# LoadCellAmp.net
KiCad netlist of a schematic drawn in EAGLE
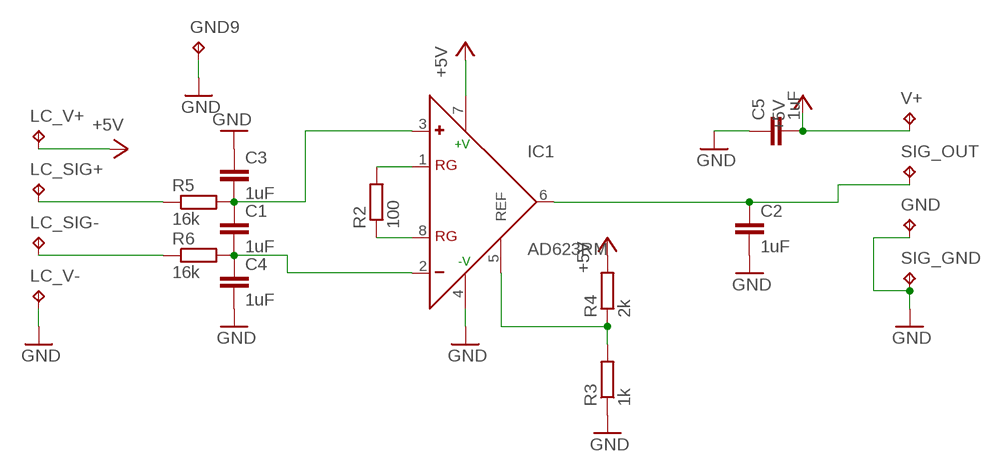
[diagram p0: schematic, sheet 1]

(export (version "E")
  (design (tool "Eeschema 10.0.6"))
  (components
    (comp (ref "C1")
      (value "1uF")
      (footprint "eagle-import:C0805")
      (libsource (lib "eagle-import") (part "C-EUC0805"))
    )
    (comp (ref "C2")
      (value "1uF")
      (footprint "eagle-import:C0805")
      (libsource (lib "eagle-import") (part "C-EUC0805"))
    )
    (comp (ref "C3")
      (value "1uF")
      (footprint "eagle-import:C0805")
      (libsource (lib "eagle-import") (part "C-EUC0805"))
    )
    (comp (ref "C4")
      (value "1uF")
      (footprint "eagle-import:C0805")
      (libsource (lib "eagle-import") (part "C-EUC0805"))
    )
    (comp (ref "C5")
      (value "1uF")
      (footprint "eagle-import:C0805")
      (libsource (lib "eagle-import") (part "C-EUC0805"))
    )
    (comp (ref "GND")
      (value "TPB1,27")
      (footprint "eagle-import:B1,27")
      (libsource (lib "eagle-import") (part "TPB1,27"))
    )
    (comp (ref "GND9")
      (value "TPB1,27")
      (footprint "eagle-import:B1,27")
      (libsource (lib "eagle-import") (part "TPB1,27"))
    )
    (comp (ref "IC1")
      (value "AD623RM")
      (footprint "eagle-import:MSOP08")
      (fields (field (name "MPN") "AD623ARMZ"))
      (libsource (lib "eagle-import") (part "AD623RM"))
    )
    (comp (ref "LC_SIG+")
      (value "TPB1,27")
      (footprint "eagle-import:B1,27")
      (libsource (lib "eagle-import") (part "TPB1,27"))
    )
    (comp (ref "LC_SIG-")
      (value "TPB1,27")
      (footprint "eagle-import:B1,27")
      (libsource (lib "eagle-import") (part "TPB1,27"))
    )
    (comp (ref "LC_V+")
      (value "TPB1,27")
      (footprint "eagle-import:B1,27")
      (libsource (lib "eagle-import") (part "TPB1,27"))
    )
    (comp (ref "LC_V-")
      (value "TPB1,27")
      (footprint "eagle-import:B1,27")
      (libsource (lib "eagle-import") (part "TPB1,27"))
    )
    (comp (ref "R2")
      (value "100")
      (footprint "eagle-import:R0805")
      (libsource (lib "eagle-import") (part "R-EU_R0805"))
    )
    (comp (ref "R3")
      (value "1k")
      (footprint "eagle-import:R0805")
      (libsource (lib "eagle-import") (part "R-EU_R0805"))
    )
    (comp (ref "R4")
      (value "2k")
      (footprint "eagle-import:R0805")
      (libsource (lib "eagle-import") (part "R-EU_R0805"))
    )
    (comp (ref "R5")
      (value "16k")
      (footprint "eagle-import:R0805")
      (libsource (lib "eagle-import") (part "R-EU_R0805"))
    )
    (comp (ref "R6")
      (value "16k")
      (footprint "eagle-import:R0805")
      (libsource (lib "eagle-import") (part "R-EU_R0805"))
    )
    (comp (ref "SIG_GND")
      (value "TPB1,27")
      (footprint "eagle-import:B1,27")
      (libsource (lib "eagle-import") (part "TPB1,27"))
    )
    (comp (ref "SIG_OUT")
      (value "TPB1,27")
      (footprint "eagle-import:B1,27")
      (libsource (lib "eagle-import") (part "TPB1,27"))
    )
    (comp (ref "V+")
      (value "TPB1,27")
      (footprint "eagle-import:B1,27")
      (libsource (lib "eagle-import") (part "TPB1,27"))
    )
  )
  (nets
    (net (code "1") (name "+5V") (class "Default")
      (node (ref "C5") (pin "2") (pinfunction "2_2") (pintype "passive"))
      (node (ref "IC1") (pin "7") (pinfunction "+V_7") (pintype "power_in"))
      (node (ref "LC_V+") (pin "TP") (pinfunction "TP_TP") (pintype "input"))
      (node (ref "R4") (pin "2") (pinfunction "2_2") (pintype "passive"))
      (node (ref "V+") (pin "TP") (pinfunction "TP_TP") (pintype "input"))
    )
    (net (code "2") (name "GND") (class "Default")
      (node (ref "C2") (pin "2") (pinfunction "2_2") (pintype "passive"))
      (node (ref "C3") (pin "1") (pinfunction "1_1") (pintype "passive"))
      (node (ref "C4") (pin "2") (pinfunction "2_2") (pintype "passive"))
      (node (ref "C5") (pin "1") (pinfunction "1_1") (pintype "passive"))
      (node (ref "GND") (pin "TP") (pinfunction "TP_TP") (pintype "input"))
      (node (ref "GND9") (pin "TP") (pinfunction "TP_TP") (pintype "input"))
      (node (ref "IC1") (pin "4") (pinfunction "-V_4") (pintype "power_in"))
      (node (ref "LC_V-") (pin "TP") (pinfunction "TP_TP") (pintype "input"))
      (node (ref "R3") (pin "1") (pinfunction "1_1") (pintype "passive"))
      (node (ref "SIG_GND") (pin "TP") (pinfunction "TP_TP") (pintype "input"))
    )
    (net (code "3") (name "Net-(IC1-+)") (class "Default")
      (node (ref "C1") (pin "1") (pinfunction "1_1") (pintype "passive"))
      (node (ref "C3") (pin "2") (pinfunction "2_2") (pintype "passive"))
      (node (ref "IC1") (pin "3") (pinfunction "+_3") (pintype "input"))
      (node (ref "R5") (pin "2") (pinfunction "2_2") (pintype "passive"))
    )
    (net (code "4") (name "Net-(IC1--)") (class "Default")
      (node (ref "C1") (pin "2") (pinfunction "2_2") (pintype "passive"))
      (node (ref "C4") (pin "1") (pinfunction "1_1") (pintype "passive"))
      (node (ref "IC1") (pin "2") (pinfunction "-_2") (pintype "input"))
      (node (ref "R6") (pin "2") (pinfunction "2_2") (pintype "passive"))
    )
    (net (code "5") (name "Net-(IC1-OUT)") (class "Default")
      (node (ref "C2") (pin "1") (pinfunction "1_1") (pintype "passive"))
      (node (ref "IC1") (pin "6") (pinfunction "OUT_6") (pintype "output"))
      (node (ref "SIG_OUT") (pin "TP") (pinfunction "TP_TP") (pintype "input"))
    )
    (net (code "6") (name "Net-(IC1-REF)") (class "Default")
      (node (ref "IC1") (pin "5") (pinfunction "REF_5") (pintype "passive"))
      (node (ref "R3") (pin "2") (pinfunction "2_2") (pintype "passive"))
      (node (ref "R4") (pin "1") (pinfunction "1_1") (pintype "passive"))
    )
    (net (code "7") (name "Net-(IC1-RG-Pad1)") (class "Default")
      (node (ref "IC1") (pin "1") (pinfunction "RG_1") (pintype "passive"))
      (node (ref "R2") (pin "2") (pinfunction "2_2") (pintype "passive"))
    )
    (net (code "8") (name "Net-(IC1-RG-Pad8)") (class "Default")
      (node (ref "IC1") (pin "8") (pinfunction "RG_8") (pintype "passive"))
      (node (ref "R2") (pin "1") (pinfunction "1_1") (pintype "passive"))
    )
    (net (code "9") (name "Net-(LC_SIG+-PadTP)") (class "Default")
      (node (ref "LC_SIG+") (pin "TP") (pinfunction "TP_TP") (pintype "input"))
      (node (ref "R5") (pin "1") (pinfunction "1_1") (pintype "passive"))
    )
    (net (code "10") (name "Net-(LC_SIG--PadTP)") (class "Default")
      (node (ref "LC_SIG-") (pin "TP") (pinfunction "TP_TP") (pintype "input"))
      (node (ref "R6") (pin "1") (pinfunction "1_1") (pintype "passive"))
    )
  )
)
